# Shield_Pi_Xbee.net
KiCad netlist of a schematic drawn in Altium Designer
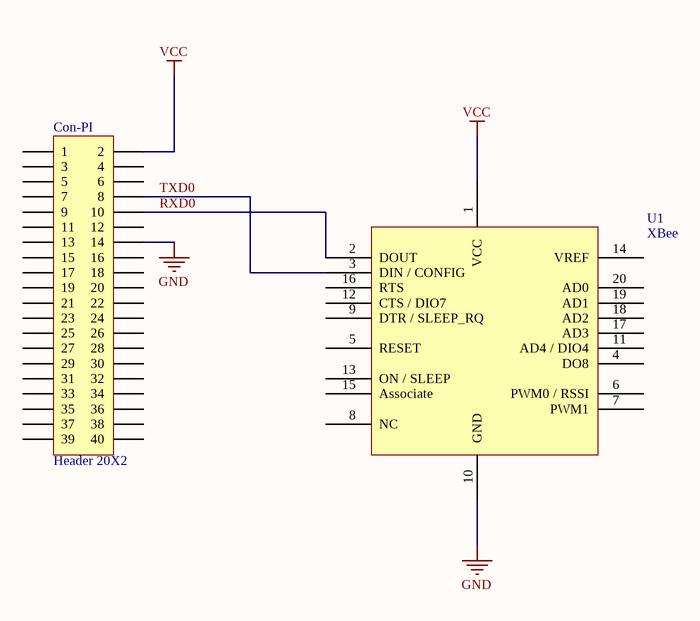
[diagram p0: Shield_Pi_Xbee.SchDoc]

(export (version "E")
  (design (tool "Eeschema 10.0.6"))
  (components
    (comp (ref "Con-PI")
      (value "Header 20X2")
      (footprint "HDR2X20")
      (description "Header, 20-Pin, Dual row")
      (fields (field (name "PUBLISHER") "Altium Limited"))
      (libsource (lib "Miscellaneous Connectors") (part "Header 20X2"))
    )
    (comp (ref "U1")
      (value "XBee")
      (footprint "XBee")
      (description "Xbee RF transceiver from Digi")
      (libsource (lib "INSA") (part "XBee"))
    )
  )
  (nets
    (net (code "1") (name "/RXD0") (class "Default")
      (node (ref "Con-PI") (pin "10") (pinfunction "10_10") (pintype "passive"))
      (node (ref "U1") (pin "2") (pinfunction "DOUT_2") (pintype "passive"))
    )
    (net (code "2") (name "/TXD0") (class "Default")
      (node (ref "Con-PI") (pin "8") (pinfunction "8_8") (pintype "passive"))
      (node (ref "U1") (pin "3") (pinfunction "DIN_/_CONFIG_3") (pintype "passive"))
    )
    (net (code "3") (name "GND") (class "Default")
      (node (ref "Con-PI") (pin "14") (pinfunction "14_14") (pintype "passive"))
      (node (ref "U1") (pin "10") (pinfunction "GND_10") (pintype "passive"))
    )
    (net (code "4") (name "VCC") (class "Default")
      (node (ref "Con-PI") (pin "2") (pinfunction "2_2") (pintype "passive"))
      (node (ref "U1") (pin "1") (pinfunction "VCC_1") (pintype "passive"))
    )
    (net (code "5") (name "unconnected-(Con-PI-Pad1)") (class "Default")
      (node (ref "Con-PI") (pin "1") (pinfunction "1_1") (pintype "passive"))
    )
    (net (code "6") (name "unconnected-(Con-PI-Pad3)") (class "Default")
      (node (ref "Con-PI") (pin "3") (pinfunction "3_3") (pintype "passive"))
    )
    (net (code "7") (name "unconnected-(Con-PI-Pad4)") (class "Default")
      (node (ref "Con-PI") (pin "4") (pinfunction "4_4") (pintype "passive"))
    )
    (net (code "8") (name "unconnected-(Con-PI-Pad5)") (class "Default")
      (node (ref "Con-PI") (pin "5") (pinfunction "5_5") (pintype "passive"))
    )
    (net (code "9") (name "unconnected-(Con-PI-Pad6)") (class "Default")
      (node (ref "Con-PI") (pin "6") (pinfunction "6_6") (pintype "passive"))
    )
    (net (code "10") (name "unconnected-(Con-PI-Pad7)") (class "Default")
      (node (ref "Con-PI") (pin "7") (pinfunction "7_7") (pintype "passive"))
    )
    (net (code "11") (name "unconnected-(Con-PI-Pad9)") (class "Default")
      (node (ref "Con-PI") (pin "9") (pinfunction "9_9") (pintype "passive"))
    )
    (net (code "12") (name "unconnected-(Con-PI-Pad11)") (class "Default")
      (node (ref "Con-PI") (pin "11") (pinfunction "11_11") (pintype "passive"))
    )
    (net (code "13") (name "unconnected-(Con-PI-Pad12)") (class "Default")
      (node (ref "Con-PI") (pin "12") (pinfunction "12_12") (pintype "passive"))
    )
    (net (code "14") (name "unconnected-(Con-PI-Pad13)") (class "Default")
      (node (ref "Con-PI") (pin "13") (pinfunction "13_13") (pintype "passive"))
    )
    (net (code "15") (name "unconnected-(Con-PI-Pad15)") (class "Default")
      (node (ref "Con-PI") (pin "15") (pinfunction "15_15") (pintype "passive"))
    )
    (net (code "16") (name "unconnected-(Con-PI-Pad16)") (class "Default")
      (node (ref "Con-PI") (pin "16") (pinfunction "16_16") (pintype "passive"))
    )
    (net (code "17") (name "unconnected-(Con-PI-Pad17)") (class "Default")
      (node (ref "Con-PI") (pin "17") (pinfunction "17_17") (pintype "passive"))
    )
    (net (code "18") (name "unconnected-(Con-PI-Pad18)") (class "Default")
      (node (ref "Con-PI") (pin "18") (pinfunction "18_18") (pintype "passive"))
    )
    (net (code "19") (name "unconnected-(Con-PI-Pad19)") (class "Default")
      (node (ref "Con-PI") (pin "19") (pinfunction "19_19") (pintype "passive"))
    )
    (net (code "20") (name "unconnected-(Con-PI-Pad20)") (class "Default")
      (node (ref "Con-PI") (pin "20") (pinfunction "20_20") (pintype "passive"))
    )
    (net (code "21") (name "unconnected-(Con-PI-Pad21)") (class "Default")
      (node (ref "Con-PI") (pin "21") (pinfunction "21_21") (pintype "passive"))
    )
    (net (code "22") (name "unconnected-(Con-PI-Pad22)") (class "Default")
      (node (ref "Con-PI") (pin "22") (pinfunction "22_22") (pintype "passive"))
    )
    (net (code "23") (name "unconnected-(Con-PI-Pad23)") (class "Default")
      (node (ref "Con-PI") (pin "23") (pinfunction "23_23") (pintype "passive"))
    )
    (net (code "24") (name "unconnected-(Con-PI-Pad24)") (class "Default")
      (node (ref "Con-PI") (pin "24") (pinfunction "24_24") (pintype "passive"))
    )
    (net (code "25") (name "unconnected-(Con-PI-Pad25)") (class "Default")
      (node (ref "Con-PI") (pin "25") (pinfunction "25_25") (pintype "passive"))
    )
    (net (code "26") (name "unconnected-(Con-PI-Pad26)") (class "Default")
      (node (ref "Con-PI") (pin "26") (pinfunction "26_26") (pintype "passive"))
    )
    (net (code "27") (name "unconnected-(Con-PI-Pad27)") (class "Default")
      (node (ref "Con-PI") (pin "27") (pinfunction "27_27") (pintype "passive"))
    )
    (net (code "28") (name "unconnected-(Con-PI-Pad28)") (class "Default")
      (node (ref "Con-PI") (pin "28") (pinfunction "28_28") (pintype "passive"))
    )
    (net (code "29") (name "unconnected-(Con-PI-Pad29)") (class "Default")
      (node (ref "Con-PI") (pin "29") (pinfunction "29_29") (pintype "passive"))
    )
    (net (code "30") (name "unconnected-(Con-PI-Pad30)") (class "Default")
      (node (ref "Con-PI") (pin "30") (pinfunction "30_30") (pintype "passive"))
    )
    (net (code "31") (name "unconnected-(Con-PI-Pad31)") (class "Default")
      (node (ref "Con-PI") (pin "31") (pinfunction "31_31") (pintype "passive"))
    )
    (net (code "32") (name "unconnected-(Con-PI-Pad32)") (class "Default")
      (node (ref "Con-PI") (pin "32") (pinfunction "32_32") (pintype "passive"))
    )
    (net (code "33") (name "unconnected-(Con-PI-Pad33)") (class "Default")
      (node (ref "Con-PI") (pin "33") (pinfunction "33_33") (pintype "passive"))
    )
    (net (code "34") (name "unconnected-(Con-PI-Pad34)") (class "Default")
      (node (ref "Con-PI") (pin "34") (pinfunction "34_34") (pintype "passive"))
    )
    (net (code "35") (name "unconnected-(Con-PI-Pad35)") (class "Default")
      (node (ref "Con-PI") (pin "35") (pinfunction "35_35") (pintype "passive"))
    )
    (net (code "36") (name "unconnected-(Con-PI-Pad36)") (class "Default")
      (node (ref "Con-PI") (pin "36") (pinfunction "36_36") (pintype "passive"))
    )
    (net (code "37") (name "unconnected-(Con-PI-Pad37)") (class "Default")
      (node (ref "Con-PI") (pin "37") (pinfunction "37_37") (pintype "passive"))
    )
    (net (code "38") (name "unconnected-(Con-PI-Pad38)") (class "Default")
      (node (ref "Con-PI") (pin "38") (pinfunction "38_38") (pintype "passive"))
    )
    (net (code "39") (name "unconnected-(Con-PI-Pad39)") (class "Default")
      (node (ref "Con-PI") (pin "39") (pinfunction "39_39") (pintype "passive"))
    )
    (net (code "40") (name "unconnected-(Con-PI-Pad40)") (class "Default")
      (node (ref "Con-PI") (pin "40") (pinfunction "40_40") (pintype "passive"))
    )
    (net (code "41") (name "unconnected-(U1-AD0-Pad20)") (class "Default")
      (node (ref "U1") (pin "20") (pinfunction "AD0_20") (pintype "passive"))
    )
    (net (code "42") (name "unconnected-(U1-AD1-Pad19)") (class "Default")
      (node (ref "U1") (pin "19") (pinfunction "AD1_19") (pintype "passive"))
    )
    (net (code "43") (name "unconnected-(U1-AD2-Pad18)") (class "Default")
      (node (ref "U1") (pin "18") (pinfunction "AD2_18") (pintype "passive"))
    )
    (net (code "44") (name "unconnected-(U1-AD3-Pad17)") (class "Default")
      (node (ref "U1") (pin "17") (pinfunction "AD3_17") (pintype "passive"))
    )
    (net (code "45") (name "unconnected-(U1-AD4_{slash}_DIO4-Pad11)") (class "Default")
      (node (ref "U1") (pin "11") (pinfunction "AD4_/_DIO4_11") (pintype "passive"))
    )
    (net (code "46") (name "unconnected-(U1-Associate-Pad15)") (class "Default")
      (node (ref "U1") (pin "15") (pinfunction "Associate_15") (pintype "passive"))
    )
    (net (code "47") (name "unconnected-(U1-CTS_{slash}_DIO7-Pad12)") (class "Default")
      (node (ref "U1") (pin "12") (pinfunction "CTS_/_DIO7_12") (pintype "passive"))
    )
    (net (code "48") (name "unconnected-(U1-DO8-Pad4)") (class "Default")
      (node (ref "U1") (pin "4") (pinfunction "DO8_4") (pintype "passive"))
    )
    (net (code "49") (name "unconnected-(U1-DTR_{slash}_SLEEP_RQ-Pad9)") (class "Default")
      (node (ref "U1") (pin "9") (pinfunction "DTR_/_SLEEP_RQ_9") (pintype "passive"))
    )
    (net (code "50") (name "unconnected-(U1-NC-Pad8)") (class "Default")
      (node (ref "U1") (pin "8") (pinfunction "NC_8") (pintype "passive"))
    )
    (net (code "51") (name "unconnected-(U1-ON_{slash}_SLEEP-Pad13)") (class "Default")
      (node (ref "U1") (pin "13") (pinfunction "ON_/_SLEEP_13") (pintype "passive"))
    )
    (net (code "52") (name "unconnected-(U1-PWM0_{slash}_RSSI-Pad6)") (class "Default")
      (node (ref "U1") (pin "6") (pinfunction "PWM0_/_RSSI_6") (pintype "passive"))
    )
    (net (code "53") (name "unconnected-(U1-PWM1-Pad7)") (class "Default")
      (node (ref "U1") (pin "7") (pinfunction "PWM1_7") (pintype "passive"))
    )
    (net (code "54") (name "unconnected-(U1-RESET-Pad5)") (class "Default")
      (node (ref "U1") (pin "5") (pinfunction "RESET_5") (pintype "passive"))
    )
    (net (code "55") (name "unconnected-(U1-RTS-Pad16)") (class "Default")
      (node (ref "U1") (pin "16") (pinfunction "RTS_16") (pintype "passive"))
    )
    (net (code "56") (name "unconnected-(U1-VREF-Pad14)") (class "Default")
      (node (ref "U1") (pin "14") (pinfunction "VREF_14") (pintype "passive"))
    )
  )
)
